# Amazing-All-Band-Receiver.net
KiCad netlist of a schematic drawn in EAGLE
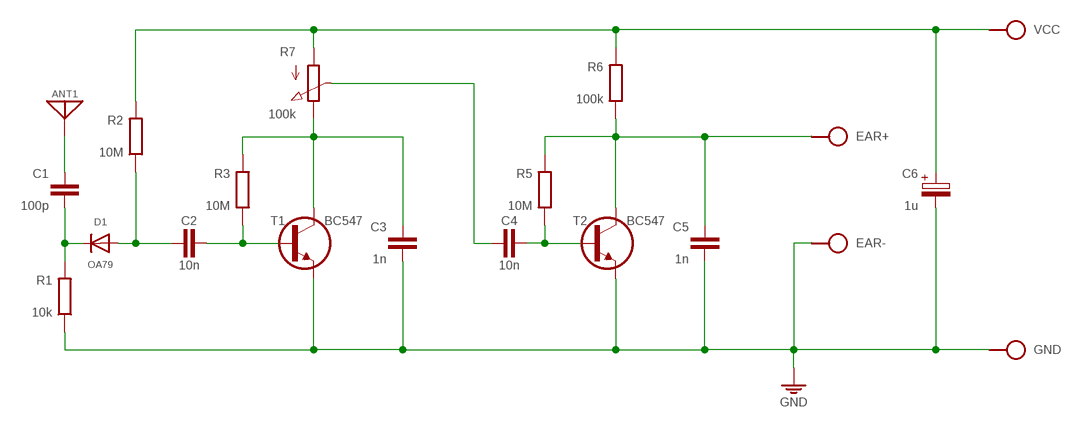
[diagram p0: schematic, sheet 1]

(export (version "E")
  (design (tool "Eeschema 10.0.6"))
  (components
    (comp (ref "ANT1")
      (value "ANT")
      (footprint "eagle-import:SPAD")
      (libsource (lib "eagle-import") (part "ANT"))
    )
    (comp (ref "C1")
      (value "100p")
      (footprint "eagle-import:C050-020X036_V")
      (libsource (lib "eagle-import") (part "C050-020X036/V"))
    )
    (comp (ref "C2")
      (value "10n")
      (footprint "eagle-import:C050-025X075")
      (libsource (lib "eagle-import") (part "C050-025X075"))
    )
    (comp (ref "C3")
      (value "1n")
      (footprint "eagle-import:C050-025X075")
      (libsource (lib "eagle-import") (part "C050-025X075"))
    )
    (comp (ref "C4")
      (value "10n")
      (footprint "eagle-import:C050-025X075")
      (libsource (lib "eagle-import") (part "C050-025X075"))
    )
    (comp (ref "C5")
      (value "1n")
      (footprint "eagle-import:C050-025X075")
      (libsource (lib "eagle-import") (part "C050-025X075"))
    )
    (comp (ref "C6")
      (value "1u")
      (footprint "eagle-import:E2,5-3")
      (libsource (lib "eagle-import") (part "CPOLE2,5-3"))
    )
    (comp (ref "D1")
      (value "OA79")
      (footprint "eagle-import:DO34-7V")
      (libsource (lib "eagle-import") (part "1N414834-7V"))
    )
    (comp (ref "EAR+")
      (value "SPAD")
      (footprint "eagle-import:SPAD")
      (libsource (lib "eagle-import") (part "SPAD"))
    )
    (comp (ref "EAR-")
      (value "SPAD")
      (footprint "eagle-import:SPAD")
      (libsource (lib "eagle-import") (part "SPAD"))
    )
    (comp (ref "GND")
      (value "SPAD")
      (footprint "eagle-import:SPAD")
      (libsource (lib "eagle-import") (part "SPAD"))
    )
    (comp (ref "R1")
      (value "10k")
      (footprint "eagle-import:0202_7-V")
      (libsource (lib "eagle-import") (part "R0202/7-V"))
    )
    (comp (ref "R2")
      (value "10M")
      (footprint "eagle-import:0202_7")
      (libsource (lib "eagle-import") (part "R0202/7"))
    )
    (comp (ref "R3")
      (value "10M")
      (footprint "eagle-import:0202_7-V")
      (libsource (lib "eagle-import") (part "R0202/7-V"))
    )
    (comp (ref "R5")
      (value "10M")
      (footprint "eagle-import:0202_7-V")
      (libsource (lib "eagle-import") (part "R0202/7-V"))
    )
    (comp (ref "R6")
      (value "100k")
      (footprint "eagle-import:0202_7-V")
      (libsource (lib "eagle-import") (part "R0202/7-V"))
    )
    (comp (ref "R7")
      (value "100k")
      (footprint "eagle-import:POT")
      (libsource (lib "eagle-import") (part "POT"))
    )
    (comp (ref "T1")
      (value "BC547")
      (footprint "eagle-import:TO92-CBE")
      (libsource (lib "eagle-import") (part "BC547CBE"))
    )
    (comp (ref "T2")
      (value "BC547")
      (footprint "eagle-import:TO92-CBE")
      (libsource (lib "eagle-import") (part "BC547CBE"))
    )
    (comp (ref "VCC")
      (value "SPAD")
      (footprint "eagle-import:SPAD")
      (libsource (lib "eagle-import") (part "SPAD"))
    )
  )
  (nets
    (net (code "1") (name "GND") (class "Default")
      (node (ref "C3") (pin "2") (pinfunction "2_2") (pintype "passive"))
      (node (ref "C5") (pin "2") (pinfunction "2_2") (pintype "passive"))
      (node (ref "C6") (pin "-") (pinfunction "-_-") (pintype "passive"))
      (node (ref "EAR-") (pin "1") (pinfunction "P$1_1") (pintype "bidirectional"))
      (node (ref "GND") (pin "1") (pinfunction "P$1_1") (pintype "bidirectional"))
      (node (ref "R1") (pin "1") (pinfunction "1_1") (pintype "passive"))
      (node (ref "T1") (pin "E") (pinfunction "E_E") (pintype "passive"))
      (node (ref "T2") (pin "E") (pinfunction "E_E") (pintype "passive"))
    )
    (net (code "2") (name "Net-(ANT1-Pad1)") (class "Default")
      (node (ref "ANT1") (pin "1") (pinfunction "1_1") (pintype "output"))
      (node (ref "C1") (pin "1") (pinfunction "1_1") (pintype "passive"))
    )
    (net (code "3") (name "Net-(C1-Pad2)") (class "Default")
      (node (ref "C1") (pin "2") (pinfunction "2_2") (pintype "passive"))
      (node (ref "D1") (pin "C") (pinfunction "C_C") (pintype "passive"))
      (node (ref "R1") (pin "2") (pinfunction "2_2") (pintype "passive"))
    )
    (net (code "4") (name "Net-(C2-Pad1)") (class "Default")
      (node (ref "C2") (pin "1") (pinfunction "1_1") (pintype "passive"))
      (node (ref "R3") (pin "1") (pinfunction "1_1") (pintype "passive"))
      (node (ref "T1") (pin "B") (pinfunction "B_B") (pintype "passive"))
    )
    (net (code "5") (name "Net-(C2-Pad2)") (class "Default")
      (node (ref "C2") (pin "2") (pinfunction "2_2") (pintype "passive"))
      (node (ref "D1") (pin "A") (pinfunction "A_A") (pintype "passive"))
      (node (ref "R2") (pin "1") (pinfunction "1_1") (pintype "passive"))
    )
    (net (code "6") (name "Net-(C4-Pad1)") (class "Default")
      (node (ref "C4") (pin "1") (pinfunction "1_1") (pintype "passive"))
      (node (ref "R5") (pin "1") (pinfunction "1_1") (pintype "passive"))
      (node (ref "T2") (pin "B") (pinfunction "B_B") (pintype "passive"))
    )
    (net (code "7") (name "Net-(EAR+-P$1)") (class "Default")
      (node (ref "C5") (pin "1") (pinfunction "1_1") (pintype "passive"))
      (node (ref "EAR+") (pin "1") (pinfunction "P$1_1") (pintype "bidirectional"))
      (node (ref "R5") (pin "2") (pinfunction "2_2") (pintype "passive"))
      (node (ref "R6") (pin "1") (pinfunction "1_1") (pintype "passive"))
      (node (ref "T2") (pin "C") (pinfunction "C_C") (pintype "passive"))
    )
    (net (code "8") (name "Net-(R7-A)") (class "Default")
      (node (ref "C6") (pin "+") (pinfunction "+_+") (pintype "passive"))
      (node (ref "R2") (pin "2") (pinfunction "2_2") (pintype "passive"))
      (node (ref "R6") (pin "2") (pinfunction "2_2") (pintype "passive"))
      (node (ref "R7") (pin "1") (pinfunction "A_1") (pintype "passive"))
      (node (ref "VCC") (pin "1") (pinfunction "P$1_1") (pintype "bidirectional"))
    )
    (net (code "9") (name "Net-(R7-E)") (class "Default")
      (node (ref "C3") (pin "1") (pinfunction "1_1") (pintype "passive"))
      (node (ref "R3") (pin "2") (pinfunction "2_2") (pintype "passive"))
      (node (ref "R7") (pin "3") (pinfunction "E_3") (pintype "passive"))
      (node (ref "T1") (pin "C") (pinfunction "C_C") (pintype "passive"))
    )
    (net (code "10") (name "Net-(R7-S)") (class "Default")
      (node (ref "C4") (pin "2") (pinfunction "2_2") (pintype "passive"))
      (node (ref "R7") (pin "2") (pinfunction "S_2") (pintype "passive"))
    )
  )
)
